# battery_monitor_6803-2_Rev3.net
KiCad netlist of a schematic drawn in EAGLE
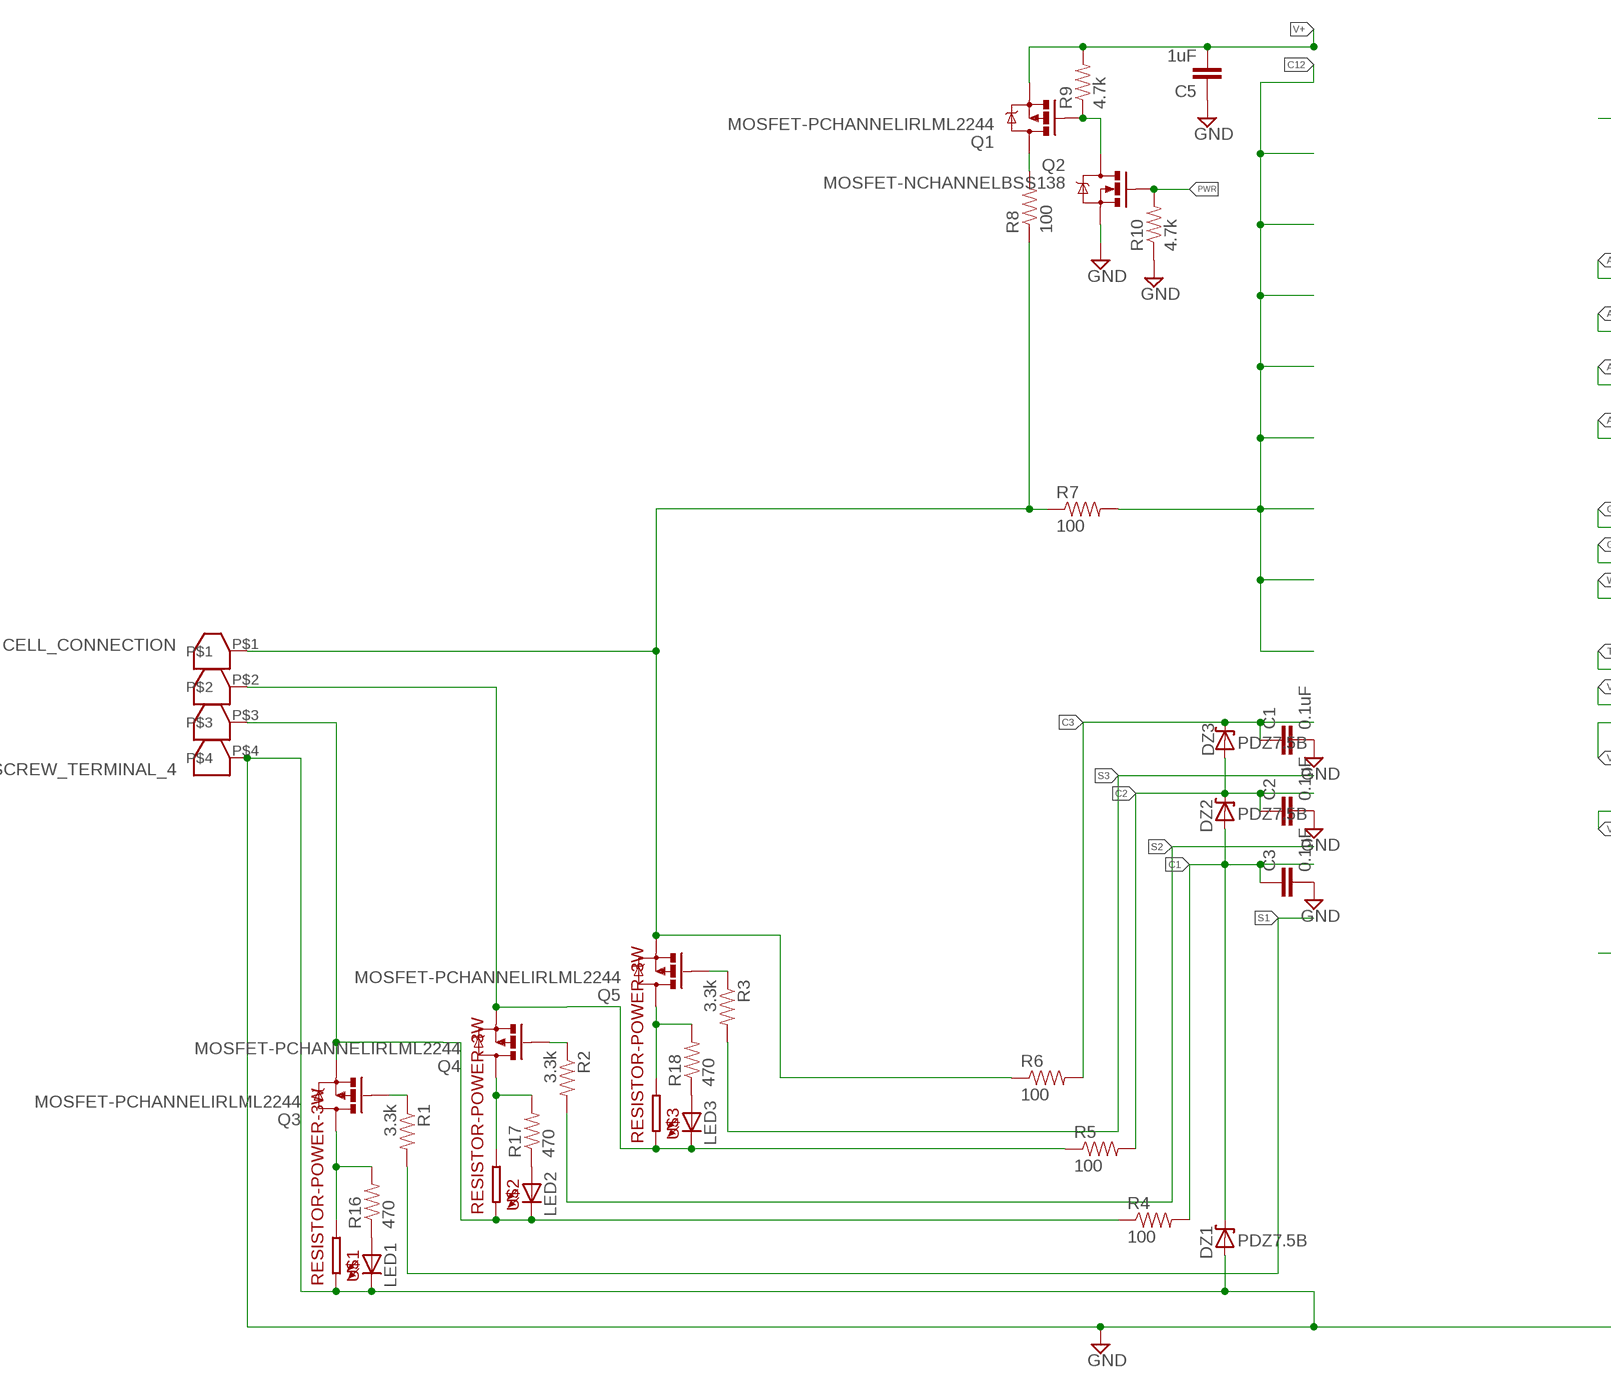
[diagram p0: schematic, sheet 1, part 1 of 2]
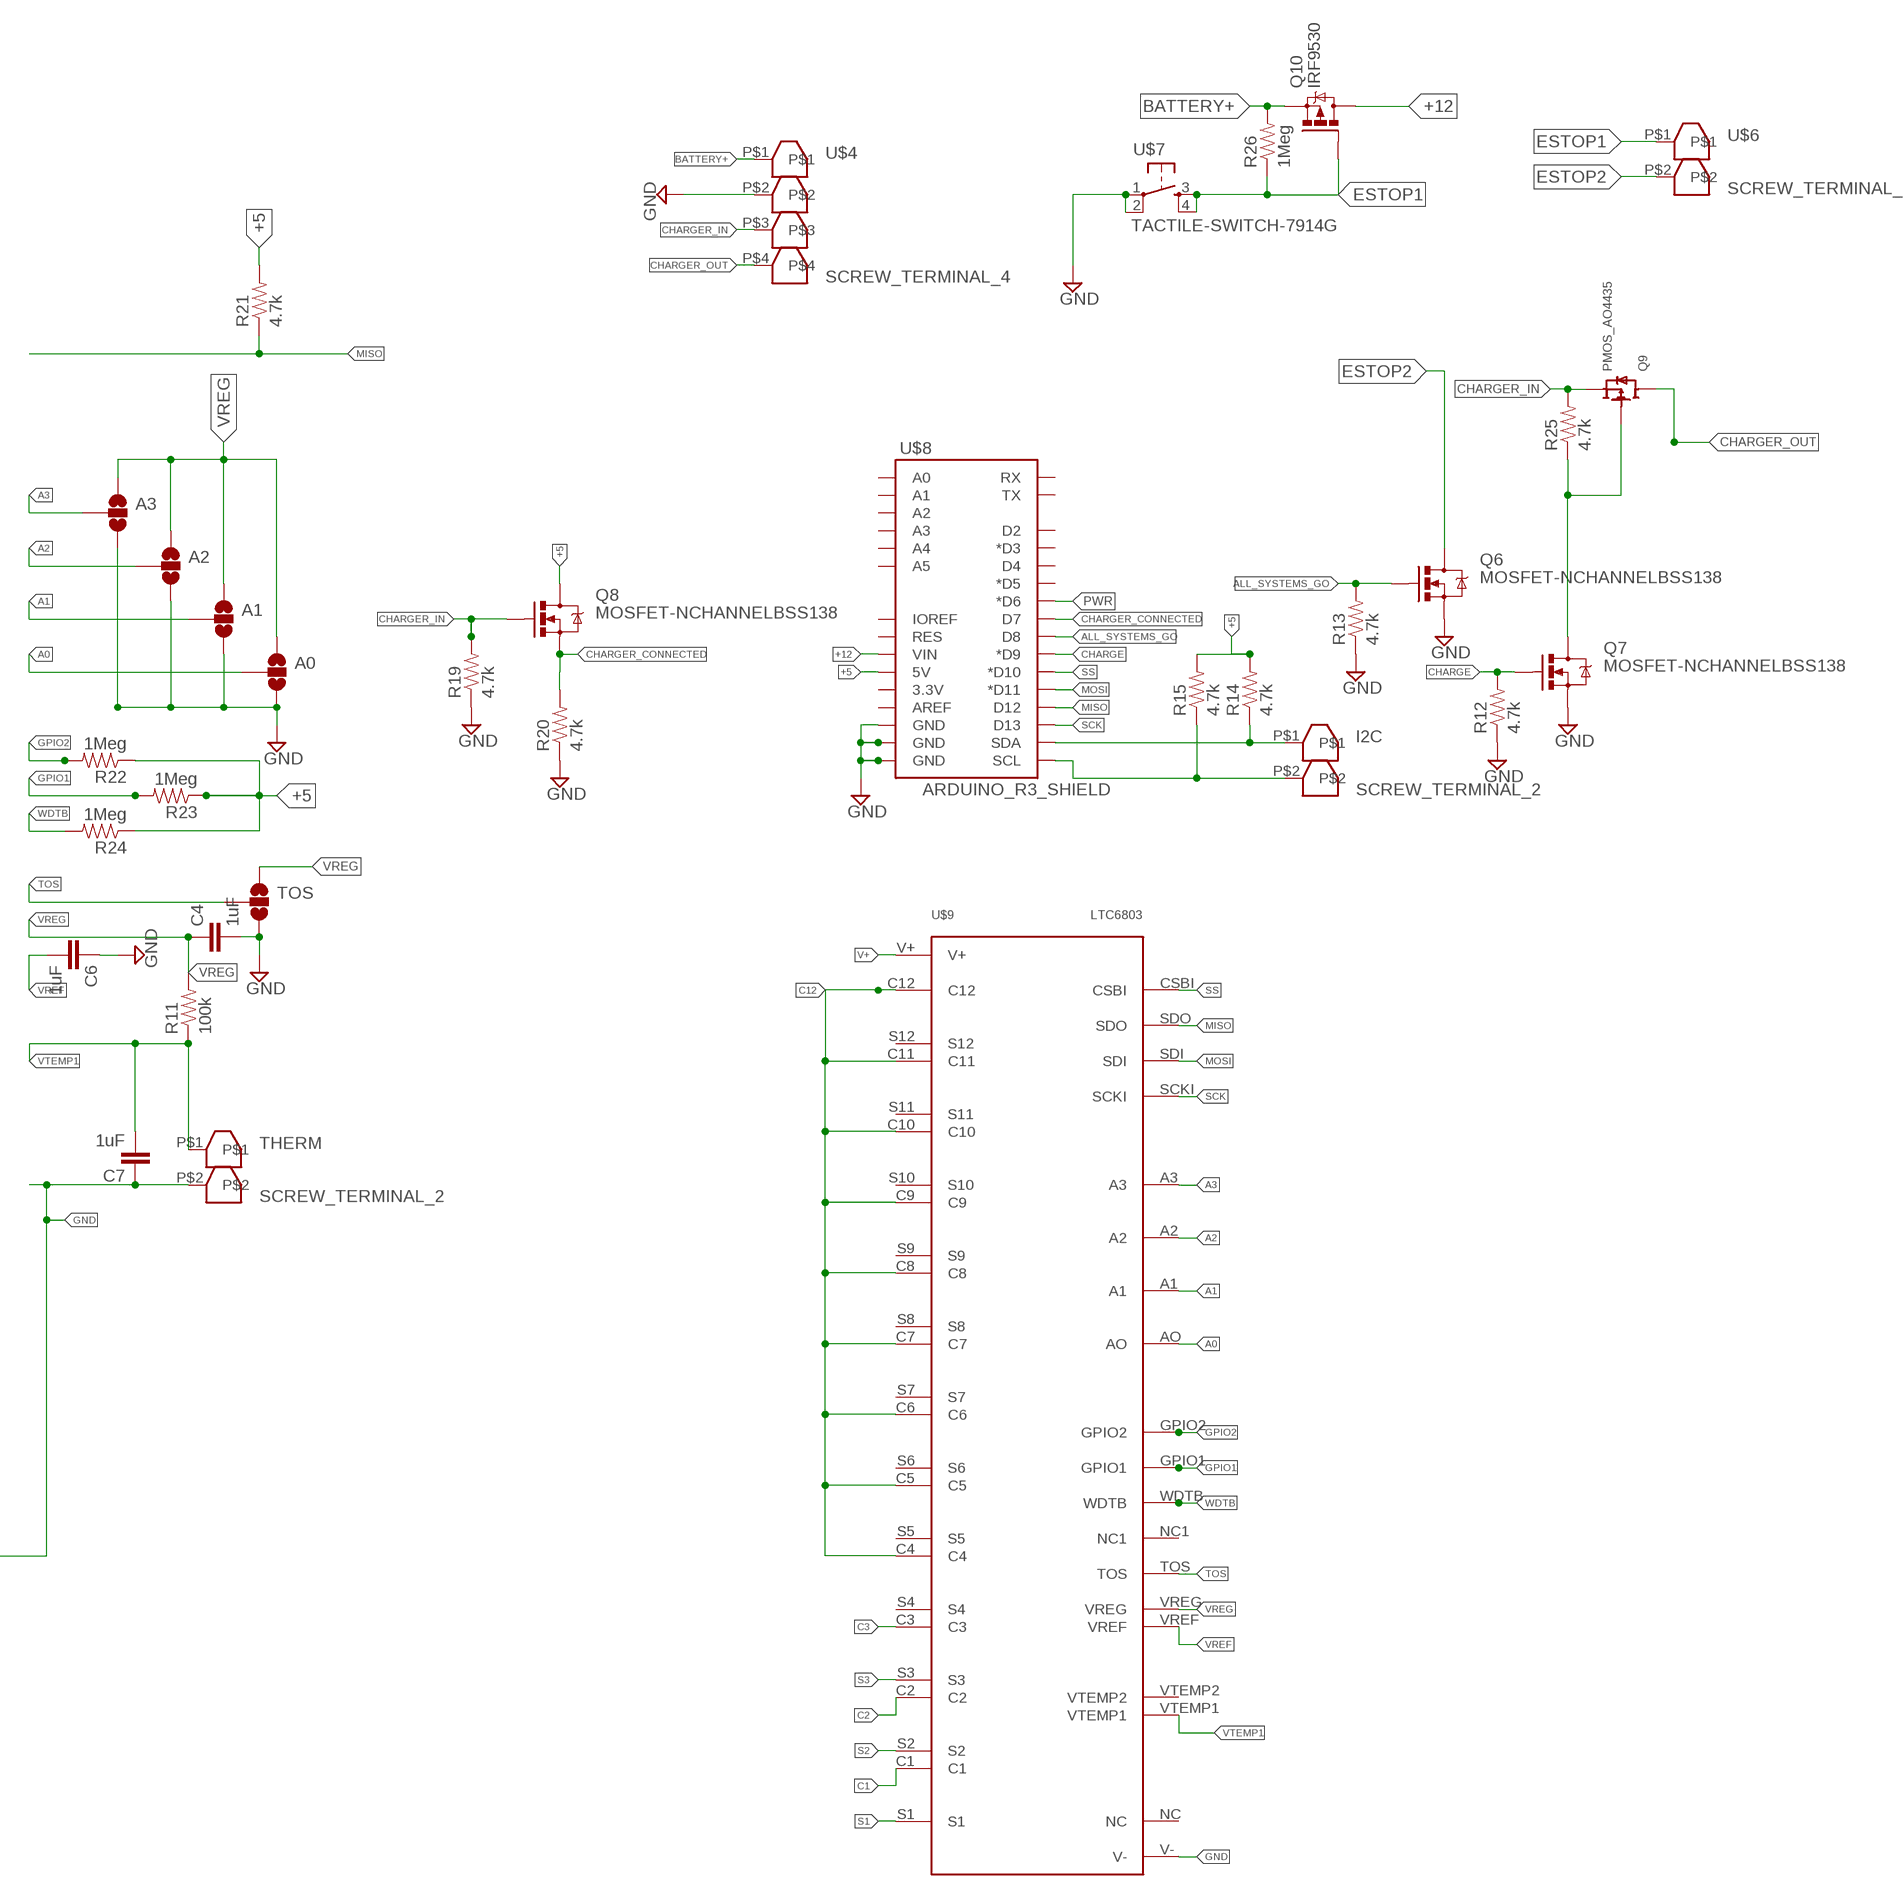
[diagram p1: schematic, sheet 1, part 2 of 2]

(export (version "E")
  (design (tool "Eeschema 10.0.6"))
  (components
    (comp (ref "A0")
      (value "SOLDERJUMPER_2WAYS")
      (footprint "eagle-import:SJ_3")
      (libsource (lib "eagle-import") (part "SOLDERJUMPER_2WAYS"))
    )
    (comp (ref "A1")
      (value "SOLDERJUMPER_2WAYS")
      (footprint "eagle-import:SJ_3")
      (libsource (lib "eagle-import") (part "SOLDERJUMPER_2WAYS"))
    )
    (comp (ref "A2")
      (value "SOLDERJUMPER_2WAYS")
      (footprint "eagle-import:SJ_3")
      (libsource (lib "eagle-import") (part "SOLDERJUMPER_2WAYS"))
    )
    (comp (ref "A3")
      (value "SOLDERJUMPER_2WAYS")
      (footprint "eagle-import:SJ_3")
      (libsource (lib "eagle-import") (part "SOLDERJUMPER_2WAYS"))
    )
    (comp (ref "C1")
      (value "0.1uF")
      (footprint "eagle-import:0603-CAP")
      (fields (field (name "MF") "AVX CORPORATION") (field (name "MPN") "0603YG104ZAT2A"))
      (libsource (lib "eagle-import") (part "0.1UF-100V-10%(0603)"))
    )
    (comp (ref "C2")
      (value "0.1uF")
      (footprint "eagle-import:0603-CAP")
      (fields (field (name "MF") "AVX CORPORATION") (field (name "MPN") "0603YG104ZAT2A"))
      (libsource (lib "eagle-import") (part "0.1UF-100V-10%(0603)"))
    )
    (comp (ref "C3")
      (value "0.1uF")
      (footprint "eagle-import:0603-CAP")
      (fields (field (name "MF") "AVX CORPORATION") (field (name "MPN") "0603YG104ZAT2A"))
      (libsource (lib "eagle-import") (part "0.1UF-100V-10%(0603)"))
    )
    (comp (ref "C4")
      (value "1uF")
      (footprint "eagle-import:0603-CAP")
      (fields (field (name "MPN") "C0603X5R0J105M030BC") (field (name "PROD_ID") "CAP-08390"))
      (libsource (lib "eagle-import") (part "0.1UF-100V-10%(0603)"))
    )
    (comp (ref "C5")
      (value "1uF")
      (footprint "eagle-import:0603-CAP")
      (fields (field (name "MPN") "C0603X5R0J105M030BC") (field (name "PROD_ID") "CAP-08390"))
      (libsource (lib "eagle-import") (part "0.1UF-100V-10%(0603)"))
    )
    (comp (ref "C6")
      (value "1uF")
      (footprint "eagle-import:0603-CAP")
      (fields (field (name "MPN") "C0603X5R0J105M030BC") (field (name "PROD_ID") "CAP-08390"))
      (libsource (lib "eagle-import") (part "0.1UF-100V-10%(0603)"))
    )
    (comp (ref "C7")
      (value "1uF")
      (footprint "eagle-import:0603-CAP")
      (fields (field (name "MPN") "C0603X5R0J105M030BC") (field (name "PROD_ID") "CAP-08390"))
      (libsource (lib "eagle-import") (part "0.1UF-100V-10%(0603)"))
    )
    (comp (ref "CELL_CONNECTION")
      (value "SCREW_TERMINAL_4")
      (footprint "eagle-import:SCREW_TERMINAL_4")
      (fields (field (name "MF") "TYCO ELECTRONICS") (field (name "MPN") "282834-4"))
      (libsource (lib "eagle-import") (part "SCREW_TERMINAL_4"))
    )
    (comp (ref "DZ1")
      (value "PDZ7.5B")
      (footprint "eagle-import:SOD-323")
      (fields (field (name "MPN") "PDZ7.5B,115"))
      (libsource (lib "eagle-import") (part "DIODE-ZENER-BZT52"))
    )
    (comp (ref "DZ2")
      (value "PDZ7.5B")
      (footprint "eagle-import:SOD-323")
      (fields (field (name "MPN") "PDZ7.5B,115"))
      (libsource (lib "eagle-import") (part "DIODE-ZENER-BZT52"))
    )
    (comp (ref "DZ3")
      (value "PDZ7.5B")
      (footprint "eagle-import:SOD-323")
      (fields (field (name "MPN") "PDZ7.5B,115"))
      (libsource (lib "eagle-import") (part "DIODE-ZENER-BZT52"))
    )
    (comp (ref "I2C")
      (value "SCREW_TERMINAL_2")
      (footprint "eagle-import:SCREW_TERMINAL_2")
      (fields (field (name "MF") "TYCO ELECTRONICS") (field (name "MPN") "282834-2"))
      (libsource (lib "eagle-import") (part "isaac1_SCREW_TERMINAL_2"))
    )
    (comp (ref "LED1")
      (value "LED0603")
      (footprint "eagle-import:LED-0603")
      (fields (field (name "MPN") "150060RS75000"))
      (libsource (lib "eagle-import") (part "LED0603"))
    )
    (comp (ref "LED2")
      (value "LED0603")
      (footprint "eagle-import:LED-0603")
      (fields (field (name "MPN") "150060RS75000"))
      (libsource (lib "eagle-import") (part "LED0603"))
    )
    (comp (ref "LED3")
      (value "LED0603")
      (footprint "eagle-import:LED-0603")
      (fields (field (name "MPN") "150060RS75000"))
      (libsource (lib "eagle-import") (part "LED0603"))
    )
    (comp (ref "Q1")
      (value "MOSFET-PCHANNELIRLML2244")
      (footprint "eagle-import:SOT23-3")
      (fields (field (name "MPN") "IRLML2244TRPBF"))
      (libsource (lib "eagle-import") (part "MOSFET-PCHANNELIRLML2244"))
    )
    (comp (ref "Q2")
      (value "MOSFET-NCHANNELBSS138")
      (footprint "eagle-import:SOT23")
      (fields (field (name "MPN") "IRLML0030TRPBF"))
      (libsource (lib "eagle-import") (part "MOSFET-NCHANNELBSS138"))
    )
    (comp (ref "Q3")
      (value "MOSFET-PCHANNELIRLML2244")
      (footprint "eagle-import:SOT23-3")
      (fields (field (name "MPN") "IRLML2244TRPBF"))
      (libsource (lib "eagle-import") (part "MOSFET-PCHANNELIRLML2244"))
    )
    (comp (ref "Q4")
      (value "MOSFET-PCHANNELIRLML2244")
      (footprint "eagle-import:SOT23-3")
      (fields (field (name "MPN") "IRLML2244TRPBF"))
      (libsource (lib "eagle-import") (part "MOSFET-PCHANNELIRLML2244"))
    )
    (comp (ref "Q5")
      (value "MOSFET-PCHANNELIRLML2244")
      (footprint "eagle-import:SOT23-3")
      (fields (field (name "MPN") "IRLML2244TRPBF"))
      (libsource (lib "eagle-import") (part "MOSFET-PCHANNELIRLML2244"))
    )
    (comp (ref "Q6")
      (value "MOSFET-NCHANNELBSS138")
      (footprint "eagle-import:SOT23")
      (fields (field (name "MPN") "IRLML0030TRPBF"))
      (libsource (lib "eagle-import") (part "MOSFET-NCHANNELBSS138"))
    )
    (comp (ref "Q7")
      (value "MOSFET-NCHANNELBSS138")
      (footprint "eagle-import:SOT23")
      (fields (field (name "MPN") "IRLML0030TRPBF"))
      (libsource (lib "eagle-import") (part "MOSFET-NCHANNELBSS138"))
    )
    (comp (ref "Q8")
      (value "MOSFET-NCHANNELBSS138")
      (footprint "eagle-import:SOT23")
      (fields (field (name "MPN") "IRLML0030TRPBF") (field (name "PROD_ID") "TRANS-00830"))
      (libsource (lib "eagle-import") (part "MOSFET-NCHANNELBSS138"))
    )
    (comp (ref "Q9")
      (value "PMOS_AO4435")
      (footprint "eagle-import:SOIC8")
      (fields (field (name "MPN") "SI9407BDY-T1-GE3"))
      (libsource (lib "eagle-import") (part "PMOS_AO4435"))
    )
    (comp (ref "Q10")
      (value "IRF9530")
      (footprint "eagle-import:TO220BV")
      (fields (field (name "MPN") "NTE2383"))
      (libsource (lib "eagle-import") (part "IRF9530"))
    )
    (comp (ref "R1")
      (value "3.3k")
      (footprint "eagle-import:0603-RES")
      (fields (field (name "MF") "VISHAY/DALE") (field (name "MPN") "CRCW06033K00FKEA"))
      (libsource (lib "eagle-import") (part "3.3KOHM1/10W1%(0603)"))
    )
    (comp (ref "R2")
      (value "3.3k")
      (footprint "eagle-import:0603-RES")
      (fields (field (name "MF") "VISHAY/DALE") (field (name "MPN") "CRCW06033K00FKEA"))
      (libsource (lib "eagle-import") (part "3.3KOHM1/10W1%(0603)"))
    )
    (comp (ref "R3")
      (value "3.3k")
      (footprint "eagle-import:0603-RES")
      (fields (field (name "MF") "VISHAY/DALE") (field (name "MPN") "CRCW06033K00FKEA"))
      (libsource (lib "eagle-import") (part "3.3KOHM1/10W1%(0603)"))
    )
    (comp (ref "R4")
      (value "100")
      (footprint "eagle-import:0603-RES")
      (fields (field (name "MPN") "ERJ-1GNF1000C"))
      (libsource (lib "eagle-import") (part "3.3KOHM1/10W1%(0603)"))
    )
    (comp (ref "R5")
      (value "100")
      (footprint "eagle-import:0603-RES")
      (fields (field (name "MPN") "ERJ-1GNF1000C"))
      (libsource (lib "eagle-import") (part "3.3KOHM1/10W1%(0603)"))
    )
    (comp (ref "R6")
      (value "100")
      (footprint "eagle-import:0603-RES")
      (fields (field (name "MPN") "ERJ-1GNF1000C"))
      (libsource (lib "eagle-import") (part "3.3KOHM1/10W1%(0603)"))
    )
    (comp (ref "R7")
      (value "100")
      (footprint "eagle-import:0603-RES")
      (fields (field (name "MPN") "ERJ-1GNF1000C"))
      (libsource (lib "eagle-import") (part "3.3KOHM1/10W1%(0603)"))
    )
    (comp (ref "R8")
      (value "100")
      (footprint "eagle-import:0603-RES")
      (fields (field (name "MPN") "ERJ-1GNF1000C"))
      (libsource (lib "eagle-import") (part "3.3KOHM1/10W1%(0603)"))
    )
    (comp (ref "R9")
      (value "4.7k")
      (footprint "eagle-import:0603-RES")
      (fields (field (name "MF") "VISHAY/DALE") (field (name "MPN") "CRCW06034K70FKEA"))
      (libsource (lib "eagle-import") (part "3.3KOHM1/10W1%(0603)"))
    )
    (comp (ref "R10")
      (value "4.7k")
      (footprint "eagle-import:0603-RES")
      (fields (field (name "MF") "VISHAY/DALE") (field (name "MPN") "CRCW06034K70FKEA"))
      (libsource (lib "eagle-import") (part "3.3KOHM1/10W1%(0603)"))
    )
    (comp (ref "R11")
      (value "100k")
      (footprint "eagle-import:0603-RES")
      (fields (field (name "MF") "FARNELL") (field (name "MPN") "MC0063W06035100K"))
      (libsource (lib "eagle-import") (part "3.3KOHM1/10W1%(0603)"))
    )
    (comp (ref "R12")
      (value "4.7k")
      (footprint "eagle-import:0603-RES")
      (fields (field (name "MF") "VISHAY/DALE") (field (name "MPN") "CRCW06034K70FKEA"))
      (libsource (lib "eagle-import") (part "3.3KOHM1/10W1%(0603)"))
    )
    (comp (ref "R13")
      (value "4.7k")
      (footprint "eagle-import:0603-RES")
      (fields (field (name "MF") "VISHAY/DALE") (field (name "MPN") "CRCW06034K70FKEA"))
      (libsource (lib "eagle-import") (part "3.3KOHM1/10W1%(0603)"))
    )
    (comp (ref "R14")
      (value "4.7k")
      (footprint "eagle-import:0603-RES")
      (fields (field (name "MF") "VISHAY/DALE") (field (name "MPN") "CRCW06034K70FKEA"))
      (libsource (lib "eagle-import") (part "3.3KOHM1/10W1%(0603)"))
    )
    (comp (ref "R15")
      (value "4.7k")
      (footprint "eagle-import:0603-RES")
      (fields (field (name "MF") "VISHAY/DALE") (field (name "MPN") "CRCW06034K70FKEA"))
      (libsource (lib "eagle-import") (part "3.3KOHM1/10W1%(0603)"))
    )
    (comp (ref "R16")
      (value "470")
      (footprint "eagle-import:0603-RES")
      (fields (field (name "MPN") "ERJ-P03F4700V") (field (name "PROD_ID") "RES-07851"))
      (libsource (lib "eagle-import") (part "3.3KOHM1/10W1%(0603)"))
    )
    (comp (ref "R17")
      (value "470")
      (footprint "eagle-import:0603-RES")
      (fields (field (name "MPN") "ERJ-P03F4700V") (field (name "PROD_ID") "RES-07851"))
      (libsource (lib "eagle-import") (part "3.3KOHM1/10W1%(0603)"))
    )
    (comp (ref "R18")
      (value "470")
      (footprint "eagle-import:0603-RES")
      (fields (field (name "MPN") "ERJ-P03F4700V") (field (name "PROD_ID") "RES-07851"))
      (libsource (lib "eagle-import") (part "3.3KOHM1/10W1%(0603)"))
    )
    (comp (ref "R19")
      (value "4.7k")
      (footprint "eagle-import:0603-RES")
      (fields
        (field (name "MF") "VISHAY/DALE")
        (field (name "MPN") "CRCW06034K70FKEA")
        (field (name "PROD_ID") "RES-07851")
      )
      (libsource (lib "eagle-import") (part "3.3KOHM1/10W1%(0603)"))
    )
    (comp (ref "R20")
      (value "4.7k")
      (footprint "eagle-import:0603-RES")
      (fields
        (field (name "MF") "VISHAY/DALE")
        (field (name "MPN") "CRCW06034K70FKEA")
        (field (name "PROD_ID") "RES-07851")
      )
      (libsource (lib "eagle-import") (part "3.3KOHM1/10W1%(0603)"))
    )
    (comp (ref "R21")
      (value "4.7k")
      (footprint "eagle-import:0603-RES")
      (fields
        (field (name "MF") "VISHAY/DALE")
        (field (name "MPN") "CRCW06034K70FKEA")
        (field (name "PROD_ID") "RES-07851")
      )
      (libsource (lib "eagle-import") (part "3.3KOHM1/10W1%(0603)"))
    )
    (comp (ref "R22")
      (value "1Meg")
      (footprint "eagle-import:0603-RES")
      (fields (field (name "MPN") "ERJ-3EKF1004V") (field (name "PROD_ID") "RES-07851"))
      (libsource (lib "eagle-import") (part "3.3KOHM1/10W1%(0603)"))
    )
    (comp (ref "R23")
      (value "1Meg")
      (footprint "eagle-import:0603-RES")
      (fields (field (name "MPN") "ERJ-3EKF1004V") (field (name "PROD_ID") "RES-07851"))
      (libsource (lib "eagle-import") (part "3.3KOHM1/10W1%(0603)"))
    )
    (comp (ref "R24")
      (value "1Meg")
      (footprint "eagle-import:0603-RES")
      (fields (field (name "MPN") "ERJ-3EKF1004V") (field (name "PROD_ID") "RES-07851"))
      (libsource (lib "eagle-import") (part "3.3KOHM1/10W1%(0603)"))
    )
    (comp (ref "R25")
      (value "4.7k")
      (footprint "eagle-import:0603-RES")
      (fields
        (field (name "MF") "VISHAY/DALE")
        (field (name "MPN") "CRCW06034K70FKEA")
        (field (name "PROD_ID") "RES-07851")
      )
      (libsource (lib "eagle-import") (part "3.3KOHM1/10W1%(0603)"))
    )
    (comp (ref "R26")
      (value "1Meg")
      (footprint "eagle-import:0603-RES")
      (fields (field (name "MPN") "ERJ-3EKF1004V"))
      (libsource (lib "eagle-import") (part "3.3KOHM1/10W1%(0603)"))
    )
    (comp (ref "THERM")
      (value "SCREW_TERMINAL_2")
      (footprint "eagle-import:SCREW_TERMINAL_2")
      (fields (field (name "MF") "TYCO ELECTRONICS") (field (name "MPN") "282834-2"))
      (libsource (lib "eagle-import") (part "isaac1_SCREW_TERMINAL_2"))
    )
    (comp (ref "TOS")
      (value "SOLDERJUMPER_2WAYS")
      (footprint "eagle-import:SJ_3")
      (libsource (lib "eagle-import") (part "SOLDERJUMPER_2WAYS"))
    )
    (comp (ref "U$1")
      (value "RESISTOR-POWER-3W")
      (footprint "eagle-import:RESISTOR-3W")
      (fields (field (name "MPN") "ERG-3SJ200"))
      (libsource (lib "eagle-import") (part "RESISTOR-POWER-3W"))
    )
    (comp (ref "U$2")
      (value "RESISTOR-POWER-3W")
      (footprint "eagle-import:RESISTOR-3W")
      (fields (field (name "MPN") "ERG-3SJ200"))
      (libsource (lib "eagle-import") (part "RESISTOR-POWER-3W"))
    )
    (comp (ref "U$3")
      (value "RESISTOR-POWER-3W")
      (footprint "eagle-import:RESISTOR-3W")
      (fields (field (name "MPN") "ERG-3SJ200"))
      (libsource (lib "eagle-import") (part "RESISTOR-POWER-3W"))
    )
    (comp (ref "U$4")
      (value "SCREW_TERMINAL_4")
      (footprint "eagle-import:SCREW_TERMINAL_4")
      (fields (field (name "MF") "TYCO ELECTRONICS") (field (name "MPN") "282834-4"))
      (libsource (lib "eagle-import") (part "SCREW_TERMINAL_4"))
    )
    (comp (ref "U$6")
      (value "SCREW_TERMINAL_2")
      (footprint "eagle-import:SCREW_TERMINAL_2")
      (fields (field (name "MF") "TYCO ELECTRONICS") (field (name "MPN") "282834-2"))
      (libsource (lib "eagle-import") (part "SCREW_TERMINAL_2"))
    )
    (comp (ref "U$7")
      (value "TACTILE-SWITCH-7914G")
      (footprint "eagle-import:7914G")
      (fields (field (name "MF") "BOURNS, INC.") (field (name "MPN") "7914G-1-000E"))
      (libsource (lib "eagle-import") (part "TACTILE-SWITCH-7914G"))
    )
    (comp (ref "U$8")
      (value "ARDUINO_R3_SHIELD")
      (footprint "eagle-import:UNO_R3_SHIELD")
      (libsource (lib "eagle-import") (part "ARDUINO_R3_SHIELD"))
    )
    (comp (ref "U$9")
      (value "LTC6803")
      (footprint "eagle-import:LTC6803_BREAKOUT")
      (fields (field (name "MPN") "LTC6803IG-2#PBF"))
      (libsource (lib "eagle-import") (part "LTC6803_BREAKOUT"))
    )
  )
  (nets
    (net (code "1") (name "+5") (class "Default")
      (node (ref "Q8") (pin "3") (pinfunction "D_3") (pintype "passive"))
      (node (ref "R14") (pin "2") (pinfunction "2_2") (pintype "passive"))
      (node (ref "R15") (pin "2") (pinfunction "2_2") (pintype "passive"))
      (node (ref "R21") (pin "2") (pinfunction "2_2") (pintype "passive"))
      (node (ref "R22") (pin "1") (pinfunction "1_1") (pintype "passive"))
      (node (ref "R23") (pin "1") (pinfunction "1_1") (pintype "passive"))
      (node (ref "R24") (pin "1") (pinfunction "1_1") (pintype "passive"))
      (node (ref "U$8") (pin "5V") (pinfunction "5V_5V") (pintype "bidirectional"))
    )
    (net (code "2") (name "+12") (class "Default")
      (node (ref "Q10") (pin "D") (pinfunction "D_D") (pintype "passive"))
      (node (ref "U$8") (pin "VIN") (pinfunction "VIN_VIN") (pintype "bidirectional"))
    )
    (net (code "3") (name "A0") (class "Default")
      (node (ref "A0") (pin "2") (pinfunction "2_2") (pintype "passive"))
      (node (ref "U$9") (pin "AO") (pinfunction "AO_AO") (pintype "bidirectional"))
    )
    (net (code "4") (name "A1") (class "Default")
      (node (ref "A1") (pin "2") (pinfunction "2_2") (pintype "passive"))
      (node (ref "U$9") (pin "A1") (pinfunction "A1_A1") (pintype "bidirectional"))
    )
    (net (code "5") (name "A2") (class "Default")
      (node (ref "A2") (pin "2") (pinfunction "2_2") (pintype "passive"))
      (node (ref "U$9") (pin "A2") (pinfunction "A2_A2") (pintype "bidirectional"))
    )
    (net (code "6") (name "A3") (class "Default")
      (node (ref "A3") (pin "2") (pinfunction "2_2") (pintype "passive"))
      (node (ref "U$9") (pin "A3") (pinfunction "A3_A3") (pintype "bidirectional"))
    )
    (net (code "7") (name "ALL_SYSTEMS_GO") (class "Default")
      (node (ref "Q6") (pin "1") (pinfunction "G_1") (pintype "passive"))
      (node (ref "R13") (pin "2") (pinfunction "2_2") (pintype "passive"))
      (node (ref "U$8") (pin "D8") (pinfunction "D8_D8") (pintype "bidirectional"))
    )
    (net (code "8") (name "BATTERY+") (class "Default")
      (node (ref "Q10") (pin "S") (pinfunction "S_S") (pintype "passive"))
      (node (ref "R26") (pin "2") (pinfunction "2_2") (pintype "passive"))
      (node (ref "U$4") (pin "P$1") (pinfunction "P$1_P$1") (pintype "bidirectional"))
    )
    (net (code "9") (name "C1") (class "Default")
      (node (ref "C3") (pin "1") (pinfunction "1_1") (pintype "passive"))
      (node (ref "DZ1") (pin "1") (pinfunction "C_1") (pintype "passive"))
      (node (ref "DZ2") (pin "2") (pinfunction "A_2") (pintype "passive"))
      (node (ref "R4") (pin "2") (pinfunction "2_2") (pintype "passive"))
      (node (ref "U$9") (pin "C1") (pinfunction "C1_C1") (pintype "bidirectional"))
    )
    (net (code "10") (name "C2") (class "Default")
      (node (ref "C2") (pin "1") (pinfunction "1_1") (pintype "passive"))
      (node (ref "DZ2") (pin "1") (pinfunction "C_1") (pintype "passive"))
      (node (ref "DZ3") (pin "2") (pinfunction "A_2") (pintype "passive"))
      (node (ref "R5") (pin "2") (pinfunction "2_2") (pintype "passive"))
      (node (ref "U$9") (pin "C2") (pinfunction "C2_C2") (pintype "bidirectional"))
    )
    (net (code "11") (name "C3") (class "Default")
      (node (ref "C1") (pin "1") (pinfunction "1_1") (pintype "passive"))
      (node (ref "DZ3") (pin "1") (pinfunction "C_1") (pintype "passive"))
      (node (ref "R6") (pin "2") (pinfunction "2_2") (pintype "passive"))
      (node (ref "U$9") (pin "C3") (pinfunction "C3_C3") (pintype "bidirectional"))
    )
    (net (code "12") (name "C12") (class "Default")
      (node (ref "R7") (pin "2") (pinfunction "2_2") (pintype "passive"))
      (node (ref "U$9") (pin "C10") (pinfunction "C10_C10") (pintype "bidirectional"))
      (node (ref "U$9") (pin "C11") (pinfunction "C11_C11") (pintype "bidirectional"))
      (node (ref "U$9") (pin "C12") (pinfunction "C12_C12") (pintype "bidirectional"))
      (node (ref "U$9") (pin "C4") (pinfunction "C4_C4") (pintype "bidirectional"))
      (node (ref "U$9") (pin "C5") (pinfunction "C5_C5") (pintype "bidirectional"))
      (node (ref "U$9") (pin "C6") (pinfunction "C6_C6") (pintype "bidirectional"))
      (node (ref "U$9") (pin "C7") (pinfunction "C7_C7") (pintype "bidirectional"))
      (node (ref "U$9") (pin "C8") (pinfunction "C8_C8") (pintype "bidirectional"))
      (node (ref "U$9") (pin "C9") (pinfunction "C9_C9") (pintype "bidirectional"))
    )
    (net (code "13") (name "CHARGE") (class "Default")
      (node (ref "Q7") (pin "1") (pinfunction "G_1") (pintype "passive"))
      (node (ref "R12") (pin "2") (pinfunction "2_2") (pintype "passive"))
      (node (ref "U$8") (pin "D9") (pinfunction "*D9_D9") (pintype "bidirectional"))
    )
    (net (code "14") (name "CHARGER_CONNECTED") (class "Default")
      (node (ref "Q8") (pin "2") (pinfunction "S_2") (pintype "passive"))
      (node (ref "R20") (pin "2") (pinfunction "2_2") (pintype "passive"))
      (node (ref "U$8") (pin "D7") (pinfunction "D7_D7") (pintype "bidirectional"))
    )
    (net (code "15") (name "CHARGER_IN") (class "Default")
      (node (ref "Q8") (pin "1") (pinfunction "G_1") (pintype "passive"))
      (node (ref "Q9") (pin "1") (pinfunction "SOURCE_1") (pintype "bidirectional"))
      (node (ref "Q9") (pin "2") (pinfunction "SOURCE_2") (pintype "bidirectional"))
      (node (ref "Q9") (pin "3") (pinfunction "SOURCE_3") (pintype "bidirectional"))
      (node (ref "R19") (pin "2") (pinfunction "2_2") (pintype "passive"))
      (node (ref "R25") (pin "2") (pinfunction "2_2") (pintype "passive"))
      (node (ref "U$4") (pin "P$3") (pinfunction "P$3_P$3") (pintype "bidirectional"))
    )
    (net (code "16") (name "CHARGER_OUT") (class "Default")
      (node (ref "Q9") (pin "5") (pinfunction "DRAIN_5") (pintype "bidirectional"))
      (node (ref "Q9") (pin "6") (pinfunction "DRAIN_6") (pintype "bidirectional"))
      (node (ref "Q9") (pin "7") (pinfunction "DRAIN_7") (pintype "bidirectional"))
      (node (ref "Q9") (pin "8") (pinfunction "DRAIN_8") (pintype "bidirectional"))
      (node (ref "U$4") (pin "P$4") (pinfunction "P$4_P$4") (pintype "bidirectional"))
    )
    (net (code "17") (name "ESTOP1") (class "Default")
      (node (ref "Q10") (pin "G") (pinfunction "G_G") (pintype "passive"))
      (node (ref "R26") (pin "1") (pinfunction "1_1") (pintype "passive"))
      (node (ref "U$6") (pin "P$1") (pinfunction "P$1_P$1") (pintype "bidirectional"))
      (node (ref "U$7") (pin "3") (pinfunction "3_3") (pintype "passive"))
      (node (ref "U$7") (pin "4") (pinfunction "4_4") (pintype "passive"))
    )
    (net (code "18") (name "ESTOP2") (class "Default")
      (node (ref "Q6") (pin "3") (pinfunction "D_3") (pintype "passive"))
      (node (ref "U$6") (pin "P$2") (pinfunction "P$2_P$2") (pintype "bidirectional"))
    )
    (net (code "19") (name "GND") (class "Default")
      (node (ref "A0") (pin "3") (pinfunction "3_3") (pintype "passive"))
      (node (ref "A1") (pin "3") (pinfunction "3_3") (pintype "passive"))
      (node (ref "A2") (pin "3") (pinfunction "3_3") (pintype "passive"))
      (node (ref "A3") (pin "3") (pinfunction "3_3") (pintype "passive"))
      (node (ref "C1") (pin "2") (pinfunction "2_2") (pintype "passive"))
      (node (ref "C2") (pin "2") (pinfunction "2_2") (pintype "passive"))
      (node (ref "C3") (pin "2") (pinfunction "2_2") (pintype "passive"))
      (node (ref "C4") (pin "2") (pinfunction "2_2") (pintype "passive"))
      (node (ref "C5") (pin "1") (pinfunction "1_1") (pintype "passive"))
      (node (ref "C6") (pin "1") (pinfunction "1_1") (pintype "passive"))
      (node (ref "C7") (pin "1") (pinfunction "1_1") (pintype "passive"))
      (node (ref "CELL_CONNECTION") (pin "P$4") (pinfunction "P$4_P$4") (pintype "bidirectional"))
      (node (ref "DZ1") (pin "2") (pinfunction "A_2") (pintype "passive"))
      (node (ref "LED1") (pin "C") (pinfunction "C_C") (pintype "passive"))
      (node (ref "Q2") (pin "2") (pinfunction "S_2") (pintype "passive"))
      (node (ref "Q6") (pin "2") (pinfunction "S_2") (pintype "passive"))
      (node (ref "Q7") (pin "2") (pinfunction "S_2") (pintype "passive"))
      (node (ref "R10") (pin "1") (pinfunction "1_1") (pintype "passive"))
      (node (ref "R12") (pin "1") (pinfunction "1_1") (pintype "passive"))
      (node (ref "R13") (pin "1") (pinfunction "1_1") (pintype "passive"))
      (node (ref "R19") (pin "1") (pinfunction "1_1") (pintype "passive"))
      (node (ref "R20") (pin "1") (pinfunction "1_1") (pintype "passive"))
      (node (ref "THERM") (pin "P$2") (pinfunction "P$2_P$2") (pintype "bidirectional"))
      (node (ref "TOS") (pin "3") (pinfunction "3_3") (pintype "passive"))
      (node (ref "U$1") (pin "P$2") (pinfunction "P$2_P$2") (pintype "bidirectional"))
      (node (ref "U$4") (pin "P$2") (pinfunction "P$2_P$2") (pintype "bidirectional"))
      (node (ref "U$7") (pin "1") (pinfunction "1_1") (pintype "passive"))
      (node (ref "U$7") (pin "2") (pinfunction "2_2") (pintype "passive"))
      (node (ref "U$8") (pin "GND@0") (pinfunction "GND_GND@0") (pintype "bidirectional"))
      (node (ref "U$8") (pin "GND@1") (pinfunction "GND_GND@1") (pintype "bidirectional"))
      (node (ref "U$8") (pin "GND@2") (pinfunction "GND_GND@2") (pintype "bidirectional"))
      (node (ref "U$9") (pin "V-") (pinfunction "V-_V-") (pintype "bidirectional"))
    )
    (net (code "20") (name "GPIO1") (class "Default")
      (node (ref "R23") (pin "2") (pinfunction "2_2") (pintype "passive"))
      (node (ref "U$9") (pin "GPIO1") (pinfunction "GPIO1_GPIO1") (pintype "bidirectional"))
    )
    (net (code "21") (name "GPIO2") (class "Default")
      (node (ref "R22") (pin "2") (pinfunction "2_2") (pintype "passive"))
      (node (ref "U$9") (pin "GPIO2") (pinfunction "GPIO2_GPIO2") (pintype "bidirectional"))
    )
    (net (code "22") (name "MISO") (class "Default")
      (node (ref "R21") (pin "1") (pinfunction "1_1") (pintype "passive"))
      (node (ref "U$8") (pin "D12") (pinfunction "D12_D12") (pintype "bidirectional"))
      (node (ref "U$9") (pin "SDO") (pinfunction "SDO_SDO") (pintype "bidirectional"))
    )
    (net (code "23") (name "MOSI") (class "Default")
      (node (ref "U$8") (pin "D11") (pinfunction "*D11_D11") (pintype "bidirectional"))
      (node (ref "U$9") (pin "SDI") (pinfunction "SDI_SDI") (pintype "bidirectional"))
    )
    (net (code "24") (name "Net-(I2C-PadP$1)") (class "Default")
      (node (ref "I2C") (pin "P$1") (pinfunction "P$1_P$1") (pintype "bidirectional"))
      (node (ref "R14") (pin "1") (pinfunction "1_1") (pintype "passive"))
      (node (ref "U$8") (pin "SDA") (pinfunction "SDA_SDA") (pintype "bidirectional"))
    )
    (net (code "25") (name "Net-(I2C-PadP$2)") (class "Default")
      (node (ref "I2C") (pin "P$2") (pinfunction "P$2_P$2") (pintype "bidirectional"))
      (node (ref "R15") (pin "1") (pinfunction "1_1") (pintype "passive"))
      (node (ref "U$8") (pin "SCL") (pinfunction "SCL_SCL") (pintype "bidirectional"))
    )
    (net (code "26") (name "Net-(LED1-PadA)") (class "Default")
      (node (ref "LED1") (pin "A") (pinfunction "A_A") (pintype "passive"))
      (node (ref "R16") (pin "1") (pinfunction "1_1") (pintype "passive"))
    )
    (net (code "27") (name "Net-(LED2-PadA)") (class "Default")
      (node (ref "LED2") (pin "A") (pinfunction "A_A") (pintype "passive"))
      (node (ref "R17") (pin "1") (pinfunction "1_1") (pintype "passive"))
    )
    (net (code "28") (name "Net-(LED3-PadA)") (class "Default")
      (node (ref "LED3") (pin "A") (pinfunction "A_A") (pintype "passive"))
      (node (ref "R18") (pin "1") (pinfunction "1_1") (pintype "passive"))
    )
    (net (code "29") (name "Net-(Q1-D)") (class "Default")
      (node (ref "Q1") (pin "3") (pinfunction "D_3") (pintype "passive"))
      (node (ref "R8") (pin "2") (pinfunction "2_2") (pintype "passive"))
    )
    (net (code "30") (name "Net-(Q1-G)") (class "Default")
      (node (ref "Q1") (pin "1") (pinfunction "G_1") (pintype "passive"))
      (node (ref "Q2") (pin "3") (pinfunction "D_3") (pintype "passive"))
      (node (ref "R9") (pin "1") (pinfunction "1_1") (pintype "passive"))
    )
    (net (code "31") (name "Net-(Q3-D)") (class "Default")
      (node (ref "Q3") (pin "3") (pinfunction "D_3") (pintype "passive"))
      (node (ref "R16") (pin "2") (pinfunction "2_2") (pintype "passive"))
      (node (ref "U$1") (pin "P$1") (pinfunction "P$1_P$1") (pintype "bidirectional"))
    )
    (net (code "32") (name "Net-(Q3-G)") (class "Default")
      (node (ref "Q3") (pin "1") (pinfunction "G_1") (pintype "passive"))
      (node (ref "R1") (pin "1") (pinfunction "1_1") (pintype "passive"))
    )
    (net (code "33") (name "Net-(Q3-S)") (class "Default")
      (node (ref "CELL_CONNECTION") (pin "P$3") (pinfunction "P$3_P$3") (pintype "bidirectional"))
      (node (ref "LED2") (pin "C") (pinfunction "C_C") (pintype "passive"))
      (node (ref "Q3") (pin "2") (pinfunction "S_2") (pintype "passive"))
      (node (ref "R4") (pin "1") (pinfunction "1_1") (pintype "passive"))
      (node (ref "U$2") (pin "P$2") (pinfunction "P$2_P$2") (pintype "bidirectional"))
    )
    (net (code "34") (name "Net-(Q4-D)") (class "Default")
      (node (ref "Q4") (pin "3") (pinfunction "D_3") (pintype "passive"))
      (node (ref "R17") (pin "2") (pinfunction "2_2") (pintype "passive"))
      (node (ref "U$2") (pin "P$1") (pinfunction "P$1_P$1") (pintype "bidirectional"))
    )
    (net (code "35") (name "Net-(Q4-G)") (class "Default")
      (node (ref "Q4") (pin "1") (pinfunction "G_1") (pintype "passive"))
      (node (ref "R2") (pin "1") (pinfunction "1_1") (pintype "passive"))
    )
    (net (code "36") (name "Net-(Q4-S)") (class "Default")
      (node (ref "CELL_CONNECTION") (pin "P$2") (pinfunction "P$2_P$2") (pintype "bidirectional"))
      (node (ref "LED3") (pin "C") (pinfunction "C_C") (pintype "passive"))
      (node (ref "Q4") (pin "2") (pinfunction "S_2") (pintype "passive"))
      (node (ref "R5") (pin "1") (pinfunction "1_1") (pintype "passive"))
      (node (ref "U$3") (pin "P$2") (pinfunction "P$2_P$2") (pintype "bidirectional"))
    )
    (net (code "37") (name "Net-(Q5-D)") (class "Default")
      (node (ref "Q5") (pin "3") (pinfunction "D_3") (pintype "passive"))
      (node (ref "R18") (pin "2") (pinfunction "2_2") (pintype "passive"))
      (node (ref "U$3") (pin "P$1") (pinfunction "P$1_P$1") (pintype "bidirectional"))
    )
    (net (code "38") (name "Net-(Q5-G)") (class "Default")
      (node (ref "Q5") (pin "1") (pinfunction "G_1") (pintype "passive"))
      (node (ref "R3") (pin "1") (pinfunction "1_1") (pintype "passive"))
    )
    (net (code "39") (name "Net-(Q5-S)") (class "Default")
      (node (ref "CELL_CONNECTION") (pin "P$1") (pinfunction "P$1_P$1") (pintype "bidirectional"))
      (node (ref "Q5") (pin "2") (pinfunction "S_2") (pintype "passive"))
      (node (ref "R6") (pin "1") (pinfunction "1_1") (pintype "passive"))
      (node (ref "R7") (pin "1") (pinfunction "1_1") (pintype "passive"))
      (node (ref "R8") (pin "1") (pinfunction "1_1") (pintype "passive"))
    )
    (net (code "40") (name "Net-(Q7-D)") (class "Default")
      (node (ref "Q7") (pin "3") (pinfunction "D_3") (pintype "passive"))
      (node (ref "Q9") (pin "4") (pinfunction "GATE_4") (pintype "bidirectional"))
      (node (ref "R25") (pin "1") (pinfunction "1_1") (pintype "passive"))
    )
    (net (code "41") (name "PWR") (class "Default")
      (node (ref "Q2") (pin "1") (pinfunction "G_1") (pintype "passive"))
      (node (ref "R10") (pin "2") (pinfunction "2_2") (pintype "passive"))
      (node (ref "U$8") (pin "D6") (pinfunction "*D6_D6") (pintype "bidirectional"))
    )
    (net (code "42") (name "S1") (class "Default")
      (node (ref "R1") (pin "2") (pinfunction "2_2") (pintype "passive"))
      (node (ref "U$9") (pin "S1") (pinfunction "S1_S1") (pintype "bidirectional"))
    )
    (net (code "43") (name "S2") (class "Default")
      (node (ref "R2") (pin "2") (pinfunction "2_2") (pintype "passive"))
      (node (ref "U$9") (pin "S2") (pinfunction "S2_S2") (pintype "bidirectional"))
    )
    (net (code "44") (name "S3") (class "Default")
      (node (ref "R3") (pin "2") (pinfunction "2_2") (pintype "passive"))
      (node (ref "U$9") (pin "S3") (pinfunction "S3_S3") (pintype "bidirectional"))
    )
    (net (code "45") (name "SCK") (class "Default")
      (node (ref "U$8") (pin "D13") (pinfunction "D13_D13") (pintype "bidirectional"))
      (node (ref "U$9") (pin "SCKI") (pinfunction "SCKI_SCKI") (pintype "bidirectional"))
    )
    (net (code "46") (name "SS") (class "Default")
      (node (ref "U$8") (pin "D10") (pinfunction "*D10_D10") (pintype "bidirectional"))
      (node (ref "U$9") (pin "CSBI") (pinfunction "CSBI_CSBI") (pintype "bidirectional"))
    )
    (net (code "47") (name "TOS") (class "Default")
      (node (ref "TOS") (pin "2") (pinfunction "2_2") (pintype "passive"))
      (node (ref "U$9") (pin "TOS") (pinfunction "TOS_TOS") (pintype "bidirectional"))
    )
    (net (code "48") (name "V+") (class "Default")
      (node (ref "C5") (pin "2") (pinfunction "2_2") (pintype "passive"))
      (node (ref "Q1") (pin "2") (pinfunction "S_2") (pintype "passive"))
      (node (ref "R9") (pin "2") (pinfunction "2_2") (pintype "passive"))
      (node (ref "U$9") (pin "V+") (pinfunction "V+_V+") (pintype "bidirectional"))
    )
    (net (code "49") (name "VREF") (class "Default")
      (node (ref "C6") (pin "2") (pinfunction "2_2") (pintype "passive"))
      (node (ref "U$9") (pin "VREF") (pinfunction "VREF_VREF") (pintype "bidirectional"))
    )
    (net (code "50") (name "VREG") (class "Default")
      (node (ref "A0") (pin "1") (pinfunction "1_1") (pintype "passive"))
      (node (ref "A1") (pin "1") (pinfunction "1_1") (pintype "passive"))
      (node (ref "A2") (pin "1") (pinfunction "1_1") (pintype "passive"))
      (node (ref "A3") (pin "1") (pinfunction "1_1") (pintype "passive"))
      (node (ref "C4") (pin "1") (pinfunction "1_1") (pintype "passive"))
      (node (ref "R11") (pin "2") (pinfunction "2_2") (pintype "passive"))
      (node (ref "TOS") (pin "1") (pinfunction "1_1") (pintype "passive"))
      (node (ref "U$9") (pin "VREG") (pinfunction "VREG_VREG") (pintype "bidirectional"))
    )
    (net (code "51") (name "VTEMP1") (class "Default")
      (node (ref "C7") (pin "2") (pinfunction "2_2") (pintype "passive"))
      (node (ref "R11") (pin "1") (pinfunction "1_1") (pintype "passive"))
      (node (ref "THERM") (pin "P$1") (pinfunction "P$1_P$1") (pintype "bidirectional"))
      (node (ref "U$9") (pin "VTEMP1") (pinfunction "VTEMP1_VTEMP1") (pintype "bidirectional"))
    )
    (net (code "52") (name "WDTB") (class "Default")
      (node (ref "R24") (pin "2") (pinfunction "2_2") (pintype "passive"))
      (node (ref "U$9") (pin "WDTB") (pinfunction "WDTB_WDTB") (pintype "bidirectional"))
    )
    (net (code "53") (name "unconnected-(U$8-*D3-PadD3)") (class "Default")
      (node (ref "U$8") (pin "D3") (pinfunction "*D3_D3") (pintype "bidirectional"))
    )
    (net (code "54") (name "unconnected-(U$8-*D5-PadD5)") (class "Default")
      (node (ref "U$8") (pin "D5") (pinfunction "*D5_D5") (pintype "bidirectional"))
    )
    (net (code "55") (name "unconnected-(U$8-Pad3.3V)") (class "Default")
      (node (ref "U$8") (pin "3.3V") (pinfunction "3.3V_3.3V") (pintype "bidirectional"))
    )
    (net (code "56") (name "unconnected-(U$8-PadA0)") (class "Default")
      (node (ref "U$8") (pin "A0") (pinfunction "A0_A0") (pintype "bidirectional"))
    )
    (net (code "57") (name "unconnected-(U$8-PadA1)") (class "Default")
      (node (ref "U$8") (pin "A1") (pinfunction "A1_A1") (pintype "bidirectional"))
    )
    (net (code "58") (name "unconnected-(U$8-PadA2)") (class "Default")
      (node (ref "U$8") (pin "A2") (pinfunction "A2_A2") (pintype "bidirectional"))
    )
    (net (code "59") (name "unconnected-(U$8-PadA3)") (class "Default")
      (node (ref "U$8") (pin "A3") (pinfunction "A3_A3") (pintype "bidirectional"))
    )
    (net (code "60") (name "unconnected-(U$8-PadA4)") (class "Default")
      (node (ref "U$8") (pin "A4") (pinfunction "A4_A4") (pintype "bidirectional"))
    )
    (net (code "61") (name "unconnected-(U$8-PadA5)") (class "Default")
      (node (ref "U$8") (pin "A5") (pinfunction "A5_A5") (pintype "bidirectional"))
    )
    (net (code "62") (name "unconnected-(U$8-PadAREF)") (class "Default")
      (node (ref "U$8") (pin "AREF") (pinfunction "AREF_AREF") (pintype "bidirectional"))
    )
    (net (code "63") (name "unconnected-(U$8-PadD2)") (class "Default")
      (node (ref "U$8") (pin "D2") (pinfunction "D2_D2") (pintype "bidirectional"))
    )
    (net (code "64") (name "unconnected-(U$8-PadD4)") (class "Default")
      (node (ref "U$8") (pin "D4") (pinfunction "D4_D4") (pintype "bidirectional"))
    )
    (net (code "65") (name "unconnected-(U$8-PadIOREF)") (class "Default")
      (node (ref "U$8") (pin "IOREF") (pinfunction "IOREF_IOREF") (pintype "bidirectional"))
    )
    (net (code "66") (name "unconnected-(U$8-PadRES)") (class "Default")
      (node (ref "U$8") (pin "RES") (pinfunction "RES_RES") (pintype "bidirectional"))
    )
    (net (code "67") (name "unconnected-(U$8-PadRX)") (class "Default")
      (node (ref "U$8") (pin "RX") (pinfunction "RX_RX") (pintype "bidirectional"))
    )
    (net (code "68") (name "unconnected-(U$8-PadTX)") (class "Default")
      (node (ref "U$8") (pin "TX") (pinfunction "TX_TX") (pintype "bidirectional"))
    )
    (net (code "69") (name "unconnected-(U$9-PadNC)") (class "Default")
      (node (ref "U$9") (pin "NC") (pinfunction "NC_NC") (pintype "bidirectional"))
    )
    (net (code "70") (name "unconnected-(U$9-PadNC1)") (class "Default")
      (node (ref "U$9") (pin "NC1") (pinfunction "NC1_NC1") (pintype "bidirectional"))
    )
    (net (code "71") (name "unconnected-(U$9-PadS4)") (class "Default")
      (node (ref "U$9") (pin "S4") (pinfunction "S4_S4") (pintype "bidirectional"))
    )
    (net (code "72") (name "unconnected-(U$9-PadS5)") (class "Default")
      (node (ref "U$9") (pin "S5") (pinfunction "S5_S5") (pintype "bidirectional"))
    )
    (net (code "73") (name "unconnected-(U$9-PadS6)") (class "Default")
      (node (ref "U$9") (pin "S6") (pinfunction "S6_S6") (pintype "bidirectional"))
    )
    (net (code "74") (name "unconnected-(U$9-PadS7)") (class "Default")
      (node (ref "U$9") (pin "S7") (pinfunction "S7_S7") (pintype "bidirectional"))
    )
    (net (code "75") (name "unconnected-(U$9-PadS8)") (class "Default")
      (node (ref "U$9") (pin "S8") (pinfunction "S8_S8") (pintype "bidirectional"))
    )
    (net (code "76") (name "unconnected-(U$9-PadS9)") (class "Default")
      (node (ref "U$9") (pin "S9") (pinfunction "S9_S9") (pintype "bidirectional"))
    )
    (net (code "77") (name "unconnected-(U$9-PadS10)") (class "Default")
      (node (ref "U$9") (pin "S10") (pinfunction "S10_S10") (pintype "bidirectional"))
    )
    (net (code "78") (name "unconnected-(U$9-PadS11)") (class "Default")
      (node (ref "U$9") (pin "S11") (pinfunction "S11_S11") (pintype "bidirectional"))
    )
    (net (code "79") (name "unconnected-(U$9-PadS12)") (class "Default")
      (node (ref "U$9") (pin "S12") (pinfunction "S12_S12") (pintype "bidirectional"))
    )
    (net (code "80") (name "unconnected-(U$9-PadVTEMP2)") (class "Default")
      (node (ref "U$9") (pin "VTEMP2") (pinfunction "VTEMP2_VTEMP2") (pintype "bidirectional"))
    )
  )
)
